# STM32.net
KiCad netlist of a schematic drawn in Altium Designer
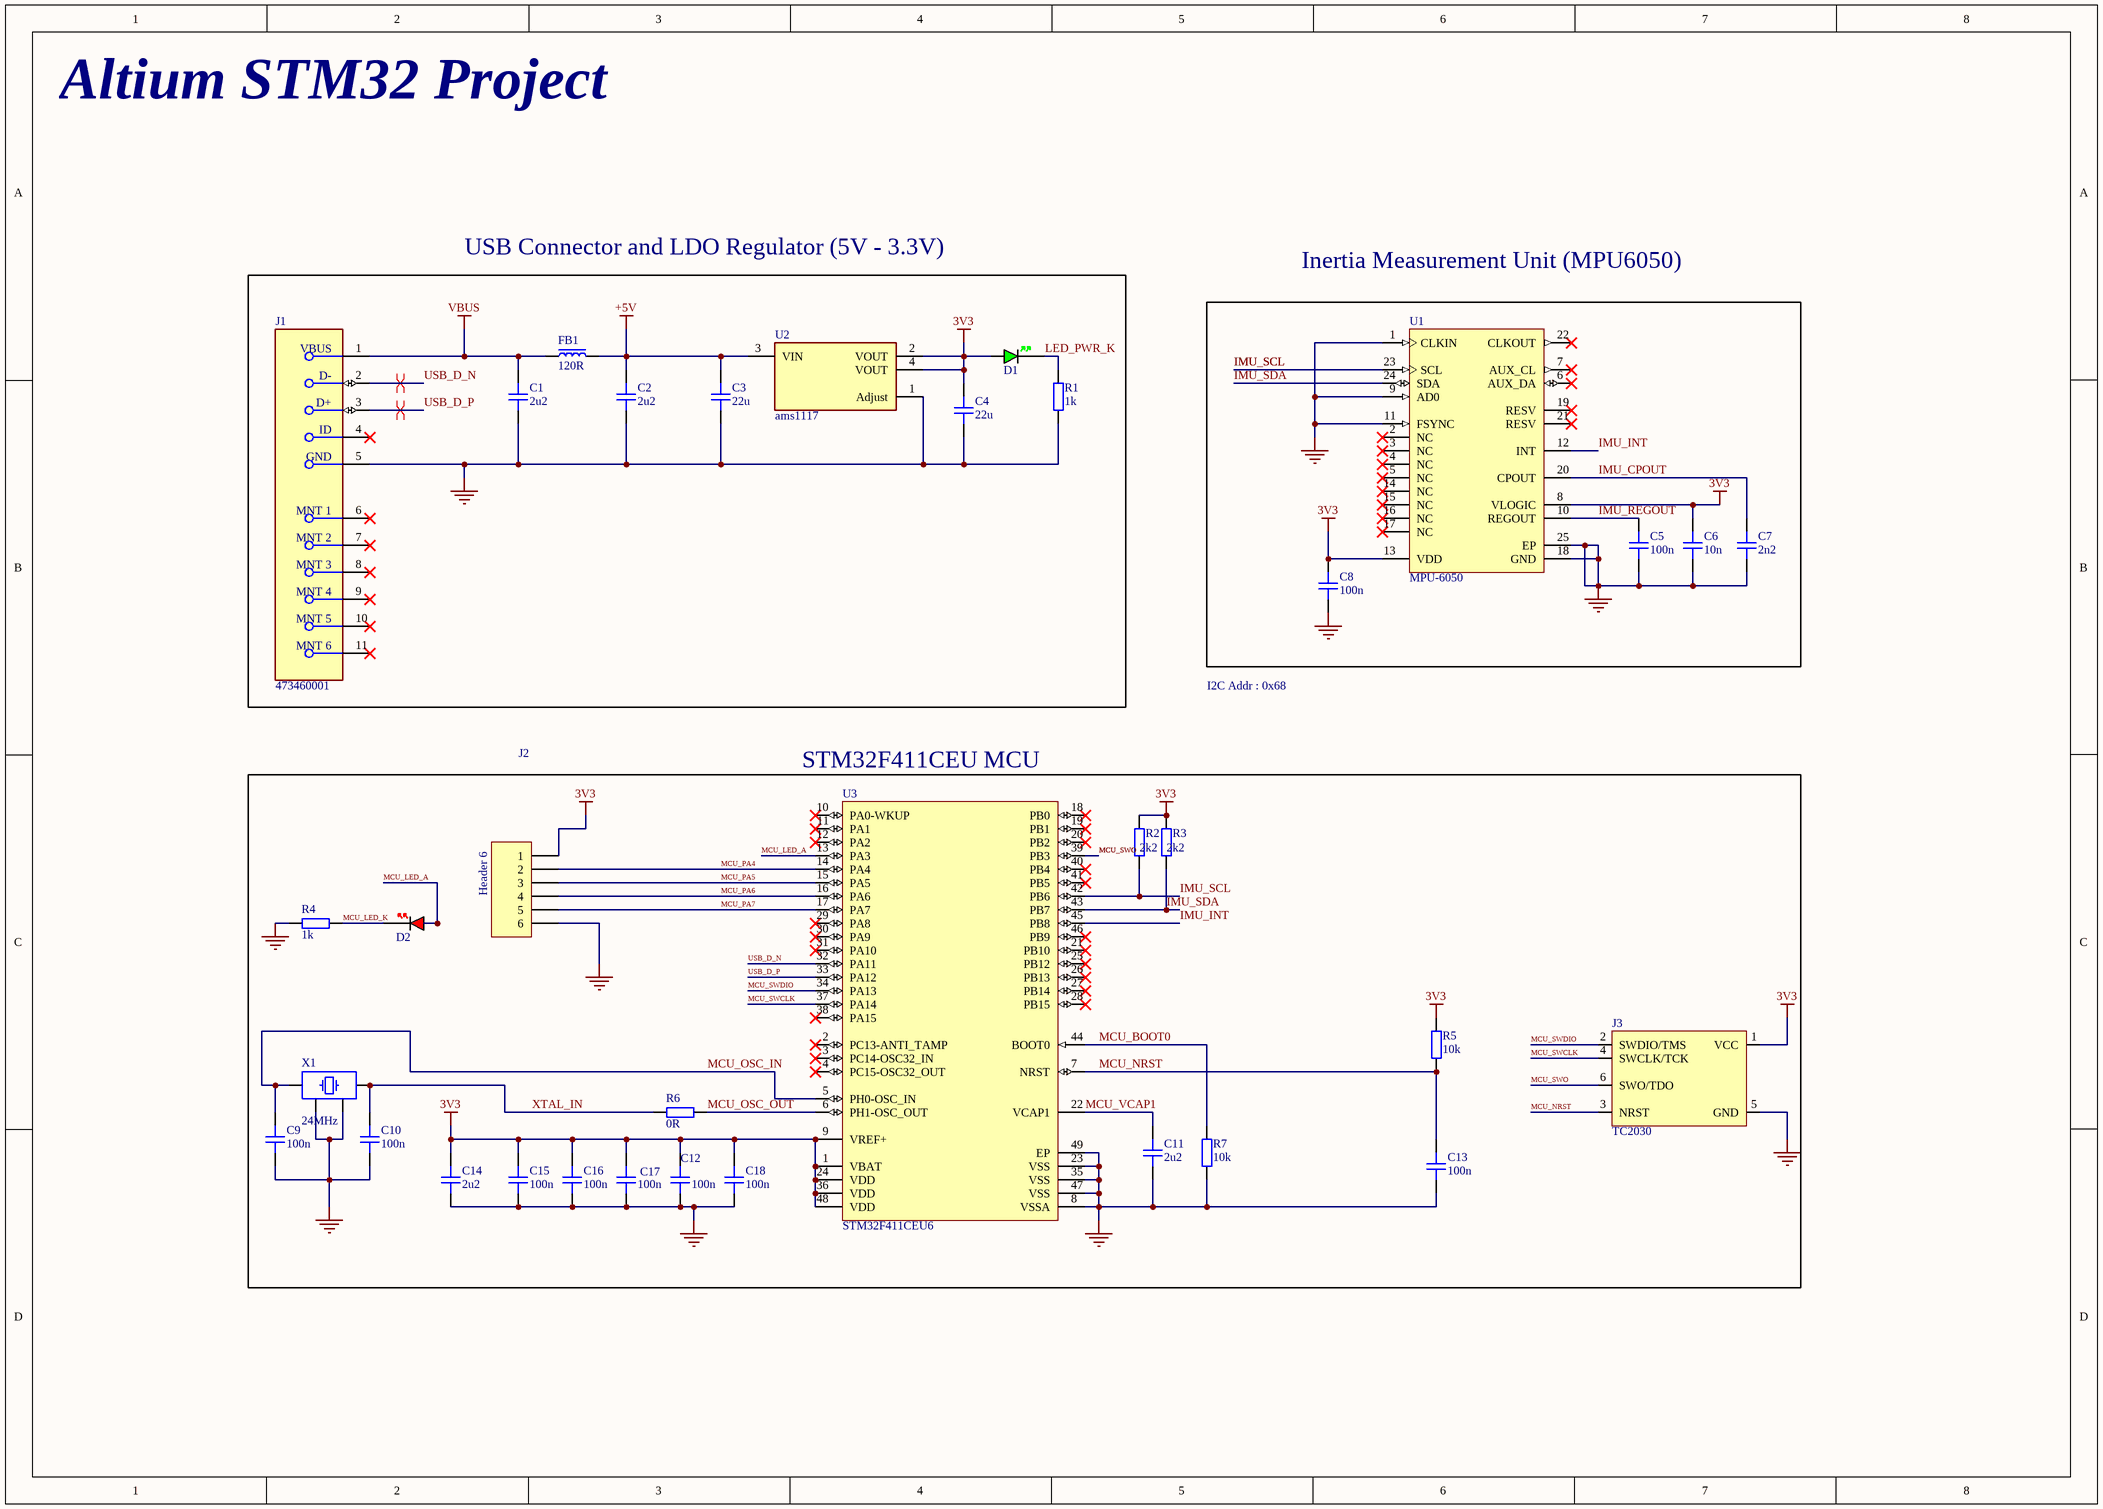
[diagram p0: STM32.SchDoc]

(export (version "E")
  (design (tool "Eeschema 10.0.6"))
  (components
    (comp (ref "C1")
      (value "2u2")
      (footprint "CAP_0603")
      (description "Capacitor SMD 0603")
      (libsource (lib "Schematic-Lib-PhilsLab") (part "CAP_0603"))
    )
    (comp (ref "C2")
      (value "2u2")
      (footprint "CAP_0603")
      (description "Capacitor SMD 0603")
      (libsource (lib "Schematic-Lib-PhilsLab") (part "CAP_0603"))
    )
    (comp (ref "C3")
      (value "22u")
      (footprint "CAP_0805")
      (description "Capacitor SMD 0805")
      (libsource (lib "Schematic-Lib-PhilsLab") (part "CAP_0805"))
    )
    (comp (ref "C4")
      (value "22u")
      (footprint "CAP_0805")
      (description "Capacitor SMD 0805")
      (libsource (lib "Schematic-Lib-PhilsLab") (part "CAP_0805"))
    )
    (comp (ref "C5")
      (value "100n")
      (footprint "CAP_0402")
      (description "Capacitor SMD 0402")
      (libsource (lib "Schematic-Lib-PhilsLab") (part "CAP_0402"))
    )
    (comp (ref "C6")
      (value "10n")
      (footprint "CAP_0402")
      (description "Capacitor SMD 0402")
      (libsource (lib "Schematic-Lib-PhilsLab") (part "CAP_0402"))
    )
    (comp (ref "C7")
      (value "2n2")
      (footprint "CAP_0402")
      (description "Capacitor SMD 0402")
      (libsource (lib "Schematic-Lib-PhilsLab") (part "CAP_0402"))
    )
    (comp (ref "C8")
      (value "100n")
      (footprint "CAP_0402")
      (description "Capacitor SMD 0402")
      (libsource (lib "Schematic-Lib-PhilsLab") (part "CAP_0402"))
    )
    (comp (ref "C9")
      (value "100n")
      (footprint "CAP_0402")
      (description "Capacitor SMD 0402")
      (libsource (lib "Schematic-Lib-PhilsLab") (part "CAP_0402"))
    )
    (comp (ref "C10")
      (value "100n")
      (footprint "CAP_0402")
      (description "Capacitor SMD 0402")
      (libsource (lib "Schematic-Lib-PhilsLab") (part "CAP_0402"))
    )
    (comp (ref "C11")
      (value "2u2")
      (footprint "CAP_0603")
      (description "Capacitor SMD 0603")
      (libsource (lib "Schematic-Lib-PhilsLab") (part "CAP_0603"))
    )
    (comp (ref "C12")
      (value "100n")
      (footprint "CAP_0402")
      (description "Capacitor SMD 0402")
      (libsource (lib "Schematic-Lib-PhilsLab") (part "CAP_0402"))
    )
    (comp (ref "C13")
      (value "100n")
      (footprint "CAP_0402")
      (description "Capacitor SMD 0402")
      (libsource (lib "Schematic-Lib-PhilsLab") (part "CAP_0402"))
    )
    (comp (ref "C14")
      (value "2u2")
      (footprint "CAP_0603")
      (description "Capacitor SMD 0603")
      (libsource (lib "Schematic-Lib-PhilsLab") (part "CAP_0603"))
    )
    (comp (ref "C15")
      (value "100n")
      (footprint "CAP_0402")
      (description "Capacitor SMD 0402")
      (libsource (lib "Schematic-Lib-PhilsLab") (part "CAP_0402"))
    )
    (comp (ref "C16")
      (value "100n")
      (footprint "CAP_0402")
      (description "Capacitor SMD 0402")
      (libsource (lib "Schematic-Lib-PhilsLab") (part "CAP_0402"))
    )
    (comp (ref "C17")
      (value "100n")
      (footprint "CAP_0402")
      (description "Capacitor SMD 0402")
      (libsource (lib "Schematic-Lib-PhilsLab") (part "CAP_0402"))
    )
    (comp (ref "C18")
      (value "100n")
      (footprint "CAP_0402")
      (description "Capacitor SMD 0402")
      (libsource (lib "Schematic-Lib-PhilsLab") (part "CAP_0402"))
    )
    (comp (ref "D1")
      (value "GREEN")
      (footprint "LED_0402_GREEN")
      (description "LED 0402 GREEN SMD")
      (libsource (lib "Schematic-Lib-PhilsLab") (part "LED_0402_GREEN"))
    )
    (comp (ref "D2")
      (value "RED")
      (footprint "LED_0402_RED")
      (description "LED 0402 RED SMD")
      (libsource (lib "Schematic-Lib-PhilsLab") (part "LED_0402_RED"))
    )
    (comp (ref "FB1")
      (value "120R")
      (footprint "FB_0603")
      (description "Ferrite Bead SMD 0603")
      (libsource (lib "Schematic-Lib-PhilsLab") (part "FB_0603"))
    )
    (comp (ref "J1")
      (value "473460001")
      (footprint "FP-473460001-MFG")
      (description "CONN RCPT USB2.0 MICRO B SMD R/A")
      (fields
        (field (name "OCTOPART") "https://octopart.com/47346-0001-molex-7164928")
        (field (name "MANUFACTURER") "Molex")
      )
      (libsource (lib "Altium Content Vault") (part "53ae1f1d9b557310b43ca686e5bb76a"))
    )
    (comp (ref "J2")
      (value "Header 6")
      (footprint "HDR1X6")
      (description "Header, 6-Pin")
      (fields (field (name "PUBLISHER") "Altium Limited"))
      (libsource (lib "Miscellaneous Connectors") (part "Header 6"))
    )
    (comp (ref "J3")
      (value "TC2030")
      (footprint "TC2030-FP")
      (description "Tag-Connect No-Solder SWD Debug Connector DO NOT PLACE")
      (fields (field (name "MANUFACTURER") "Tag-Connect"))
      (libsource (lib "Schematic-Lib-PhilsLab") (part "TC2030"))
    )
    (comp (ref "R1")
      (value "1k")
      (footprint "RES_0402")
      (description "Resistor SMD 0402")
      (libsource (lib "Schematic-Lib-PhilsLab") (part "RES_0402"))
    )
    (comp (ref "R2")
      (value "2k2")
      (footprint "RES_0402")
      (description "Resistor SMD 0402")
      (libsource (lib "Schematic-Lib-PhilsLab") (part "RES_0402"))
    )
    (comp (ref "R3")
      (value "2k2")
      (footprint "RES_0402")
      (description "Resistor SMD 0402")
      (libsource (lib "Schematic-Lib-PhilsLab") (part "RES_0402"))
    )
    (comp (ref "R4")
      (value "1k")
      (footprint "RES_0402")
      (description "Resistor SMD 0402")
      (libsource (lib "Schematic-Lib-PhilsLab") (part "RES_0402"))
    )
    (comp (ref "R5")
      (value "10k")
      (footprint "RES_0402")
      (description "Resistor SMD 0402")
      (libsource (lib "Schematic-Lib-PhilsLab") (part "RES_0402"))
    )
    (comp (ref "R6")
      (value "0R")
      (footprint "RES_0402")
      (description "Resistor SMD 0402")
      (libsource (lib "Schematic-Lib-PhilsLab") (part "RES_0402"))
    )
    (comp (ref "R7")
      (value "10k")
      (footprint "RES_0402")
      (description "Resistor SMD 0402")
      (libsource (lib "Schematic-Lib-PhilsLab") (part "RES_0402"))
    )
    (comp (ref "U1")
      (value "MPU-6050")
      (footprint "IS-QFN-24_V")
      (fields (field (name "MANUFACTURER") "InvenSense"))
      (libsource (lib "Altium Content Vault") (part "IS-MPU-6050-QFN-24"))
    )
    (comp (ref "U2")
      (value "ams1117")
      (footprint "FP-ams1117-IPC_C")
      (description "1A LOW DROPOUT VOLTAGE REGULATOR")
      (libsource (lib "Altium Content Vault") (part "59ad430b93a2c51b3e6ee7c3b069677"))
    )
    (comp (ref "U3")
      (value "STM32F411CEU6")
      (footprint "STM-UFQFPN48_L")
      (libsource (lib "Altium Content Vault") (part "MC-ARM-STM32F411-UFQFPN48"))
    )
    (comp (ref "X1")
      (value "24MHz")
      (footprint "XTAL_3225")
      (description "Crystal SMD 24MHz 10PPM 7pF 3225")
      (fields
        (field (name "MANUFACTURER") "Epson")
        (field (name "MANUFACTURER PART NUMBER") "TSX-3225 24.0000MF15X-AC")
      )
      (libsource (lib "Schematic-Lib-PhilsLab") (part "TSX-3225_24.0000MF15X-AC"))
    )
  )
  (nets
    (net (code "1") (name "+5V") (class "Default")
      (node (ref "C2") (pin "1") (pinfunction "1_1") (pintype "passive"))
      (node (ref "C3") (pin "1") (pinfunction "1_1") (pintype "passive"))
      (node (ref "FB1") (pin "2") (pinfunction "2_2") (pintype "passive"))
      (node (ref "U2") (pin "3") (pinfunction "VIN_3") (pintype "power_in"))
    )
    (net (code "2") (name "/IMU_CPOUT") (class "Default")
      (node (ref "C7") (pin "2") (pinfunction "2_2") (pintype "passive"))
      (node (ref "U1") (pin "20") (pinfunction "CPOUT_20") (pintype "passive"))
    )
    (net (code "3") (name "/IMU_INT") (class "Default")
      (node (ref "U1") (pin "12") (pinfunction "INT_12") (pintype "open_collector"))
      (node (ref "U3") (pin "45") (pinfunction "PB8_45") (pintype "bidirectional"))
    )
    (net (code "4") (name "/IMU_REGOUT") (class "Default")
      (node (ref "C5") (pin "2") (pinfunction "2_2") (pintype "passive"))
      (node (ref "U1") (pin "10") (pinfunction "REGOUT_10") (pintype "passive"))
    )
    (net (code "5") (name "/IMU_SCL") (class "Default")
      (node (ref "R2") (pin "1") (pinfunction "1_1") (pintype "passive"))
      (node (ref "U1") (pin "23") (pinfunction "SCL_23") (pintype "input"))
      (node (ref "U3") (pin "42") (pinfunction "PB6_42") (pintype "bidirectional"))
    )
    (net (code "6") (name "/IMU_SDA") (class "Default")
      (node (ref "R3") (pin "1") (pinfunction "1_1") (pintype "passive"))
      (node (ref "U1") (pin "24") (pinfunction "SDA_24") (pintype "bidirectional"))
      (node (ref "U3") (pin "43") (pinfunction "PB7_43") (pintype "bidirectional"))
    )
    (net (code "7") (name "/LED_PWR_K") (class "Default")
      (node (ref "D1") (pin "K") (pinfunction "K_K") (pintype "passive"))
      (node (ref "R1") (pin "2") (pinfunction "2_2") (pintype "passive"))
    )
    (net (code "8") (name "/MCU_BOOT0") (class "Default")
      (node (ref "R7") (pin "2") (pinfunction "2_2") (pintype "passive"))
      (node (ref "U3") (pin "44") (pinfunction "BOOT0_44") (pintype "input"))
    )
    (net (code "9") (name "/MCU_LED_A") (class "Default")
      (node (ref "D2") (pin "A") (pinfunction "A_A") (pintype "passive"))
      (node (ref "U3") (pin "13") (pinfunction "PA3_13") (pintype "bidirectional"))
    )
    (net (code "10") (name "/MCU_LED_K") (class "Default")
      (node (ref "D2") (pin "K") (pinfunction "K_K") (pintype "passive"))
      (node (ref "R4") (pin "2") (pinfunction "2_2") (pintype "passive"))
    )
    (net (code "11") (name "/MCU_NRST") (class "Default")
      (node (ref "C13") (pin "2") (pinfunction "2_2") (pintype "passive"))
      (node (ref "J3") (pin "3") (pinfunction "NRST_3") (pintype "passive"))
      (node (ref "R5") (pin "1") (pinfunction "1_1") (pintype "passive"))
      (node (ref "U3") (pin "7") (pinfunction "NRST_7") (pintype "bidirectional"))
    )
    (net (code "12") (name "/MCU_OSC_IN") (class "Default")
      (node (ref "C9") (pin "2") (pinfunction "2_2") (pintype "passive"))
      (node (ref "U3") (pin "5") (pinfunction "PH0-OSC_IN_5") (pintype "bidirectional"))
      (node (ref "X1") (pin "1") (pinfunction "1_1") (pintype "passive"))
    )
    (net (code "13") (name "/MCU_OSC_OUT") (class "Default")
      (node (ref "R6") (pin "1") (pinfunction "1_1") (pintype "passive"))
      (node (ref "U3") (pin "6") (pinfunction "PH1-OSC_OUT_6") (pintype "bidirectional"))
    )
    (net (code "14") (name "/MCU_PA4") (class "Default")
      (node (ref "J2") (pin "2") (pinfunction "2_2") (pintype "passive"))
      (node (ref "U3") (pin "14") (pinfunction "PA4_14") (pintype "bidirectional"))
    )
    (net (code "15") (name "/MCU_PA5") (class "Default")
      (node (ref "J2") (pin "3") (pinfunction "3_3") (pintype "passive"))
      (node (ref "U3") (pin "15") (pinfunction "PA5_15") (pintype "bidirectional"))
    )
    (net (code "16") (name "/MCU_PA6") (class "Default")
      (node (ref "J2") (pin "4") (pinfunction "4_4") (pintype "passive"))
      (node (ref "U3") (pin "16") (pinfunction "PA6_16") (pintype "bidirectional"))
    )
    (net (code "17") (name "/MCU_PA7") (class "Default")
      (node (ref "J2") (pin "5") (pinfunction "5_5") (pintype "passive"))
      (node (ref "U3") (pin "17") (pinfunction "PA7_17") (pintype "bidirectional"))
    )
    (net (code "18") (name "/MCU_SWCLK") (class "Default")
      (node (ref "J3") (pin "4") (pinfunction "SWCLK/TCK_4") (pintype "passive"))
      (node (ref "U3") (pin "37") (pinfunction "PA14_37") (pintype "bidirectional"))
    )
    (net (code "19") (name "/MCU_SWDIO") (class "Default")
      (node (ref "J3") (pin "2") (pinfunction "SWDIO/TMS_2") (pintype "passive"))
      (node (ref "U3") (pin "34") (pinfunction "PA13_34") (pintype "bidirectional"))
    )
    (net (code "20") (name "/MCU_SWO") (class "Default")
      (node (ref "J3") (pin "6") (pinfunction "SWO/TDO_6") (pintype "passive"))
      (node (ref "U3") (pin "39") (pinfunction "PB3_39") (pintype "bidirectional"))
    )
    (net (code "21") (name "/MCU_VCAP1") (class "Default")
      (node (ref "C11") (pin "1") (pinfunction "1_1") (pintype "passive"))
      (node (ref "U3") (pin "22") (pinfunction "VCAP1_22") (pintype "passive"))
    )
    (net (code "22") (name "/USB_D_N") (class "Default")
      (node (ref "J1") (pin "2") (pinfunction "D-_2") (pintype "bidirectional"))
      (node (ref "U3") (pin "32") (pinfunction "PA11_32") (pintype "bidirectional"))
    )
    (net (code "23") (name "/USB_D_P") (class "Default")
      (node (ref "J1") (pin "3") (pinfunction "D+_3") (pintype "bidirectional"))
      (node (ref "U3") (pin "33") (pinfunction "PA12_33") (pintype "bidirectional"))
    )
    (net (code "24") (name "/XTAL_IN") (class "Default")
      (node (ref "C10") (pin "2") (pinfunction "2_2") (pintype "passive"))
      (node (ref "R6") (pin "2") (pinfunction "2_2") (pintype "passive"))
      (node (ref "X1") (pin "3") (pinfunction "3_3") (pintype "passive"))
    )
    (net (code "25") (name "3V3") (class "Default")
      (node (ref "C12") (pin "2") (pinfunction "2_2") (pintype "passive"))
      (node (ref "C14") (pin "1") (pinfunction "1_1") (pintype "passive"))
      (node (ref "C15") (pin "2") (pinfunction "2_2") (pintype "passive"))
      (node (ref "C16") (pin "2") (pinfunction "2_2") (pintype "passive"))
      (node (ref "C17") (pin "2") (pinfunction "2_2") (pintype "passive"))
      (node (ref "C18") (pin "2") (pinfunction "2_2") (pintype "passive"))
      (node (ref "C4") (pin "1") (pinfunction "1_1") (pintype "passive"))
      (node (ref "C6") (pin "2") (pinfunction "2_2") (pintype "passive"))
      (node (ref "C8") (pin "2") (pinfunction "2_2") (pintype "passive"))
      (node (ref "D1") (pin "A") (pinfunction "A_A") (pintype "passive"))
      (node (ref "J2") (pin "1") (pinfunction "1_1") (pintype "passive"))
      (node (ref "J3") (pin "1") (pinfunction "VCC_1") (pintype "passive"))
      (node (ref "R2") (pin "2") (pinfunction "2_2") (pintype "passive"))
      (node (ref "R3") (pin "2") (pinfunction "2_2") (pintype "passive"))
      (node (ref "R5") (pin "2") (pinfunction "2_2") (pintype "passive"))
      (node (ref "U1") (pin "13") (pinfunction "VDD_13") (pintype "power_in"))
      (node (ref "U1") (pin "8") (pinfunction "VLOGIC_8") (pintype "power_in"))
      (node (ref "U2") (pin "2") (pinfunction "VOUT_2") (pintype "passive"))
      (node (ref "U2") (pin "4") (pinfunction "VOUT_4") (pintype "passive"))
      (node (ref "U3") (pin "1") (pinfunction "VBAT_1") (pintype "power_in"))
      (node (ref "U3") (pin "24") (pinfunction "VDD_24") (pintype "power_in"))
      (node (ref "U3") (pin "36") (pinfunction "VDD_36") (pintype "power_in"))
      (node (ref "U3") (pin "48") (pinfunction "VDD_48") (pintype "power_in"))
      (node (ref "U3") (pin "9") (pinfunction "VREF+_9") (pintype "power_in"))
    )
    (net (code "26") (name "GND") (class "Default")
      (node (ref "C1") (pin "2") (pinfunction "2_2") (pintype "passive"))
      (node (ref "C10") (pin "1") (pinfunction "1_1") (pintype "passive"))
      (node (ref "C11") (pin "2") (pinfunction "2_2") (pintype "passive"))
      (node (ref "C12") (pin "1") (pinfunction "1_1") (pintype "passive"))
      (node (ref "C13") (pin "1") (pinfunction "1_1") (pintype "passive"))
      (node (ref "C14") (pin "2") (pinfunction "2_2") (pintype "passive"))
      (node (ref "C15") (pin "1") (pinfunction "1_1") (pintype "passive"))
      (node (ref "C16") (pin "1") (pinfunction "1_1") (pintype "passive"))
      (node (ref "C17") (pin "1") (pinfunction "1_1") (pintype "passive"))
      (node (ref "C18") (pin "1") (pinfunction "1_1") (pintype "passive"))
      (node (ref "C2") (pin "2") (pinfunction "2_2") (pintype "passive"))
      (node (ref "C3") (pin "2") (pinfunction "2_2") (pintype "passive"))
      (node (ref "C4") (pin "2") (pinfunction "2_2") (pintype "passive"))
      (node (ref "C5") (pin "1") (pinfunction "1_1") (pintype "passive"))
      (node (ref "C6") (pin "1") (pinfunction "1_1") (pintype "passive"))
      (node (ref "C7") (pin "1") (pinfunction "1_1") (pintype "passive"))
      (node (ref "C8") (pin "1") (pinfunction "1_1") (pintype "passive"))
      (node (ref "C9") (pin "1") (pinfunction "1_1") (pintype "passive"))
      (node (ref "J1") (pin "5") (pinfunction "GND_5") (pintype "power_in"))
      (node (ref "J2") (pin "6") (pinfunction "6_6") (pintype "passive"))
      (node (ref "J3") (pin "5") (pinfunction "GND_5") (pintype "passive"))
      (node (ref "R1") (pin "1") (pinfunction "1_1") (pintype "passive"))
      (node (ref "R4") (pin "1") (pinfunction "1_1") (pintype "passive"))
      (node (ref "R7") (pin "1") (pinfunction "1_1") (pintype "passive"))
      (node (ref "U1") (pin "1") (pinfunction "CLKIN_1") (pintype "input"))
      (node (ref "U1") (pin "11") (pinfunction "FSYNC_11") (pintype "input"))
      (node (ref "U1") (pin "18") (pinfunction "GND_18") (pintype "power_in"))
      (node (ref "U1") (pin "25") (pinfunction "EP_25") (pintype "power_in"))
      (node (ref "U1") (pin "9") (pinfunction "AD0_9") (pintype "input"))
      (node (ref "U2") (pin "1") (pinfunction "Adjust_1") (pintype "passive"))
      (node (ref "U3") (pin "23") (pinfunction "VSS_23") (pintype "power_in"))
      (node (ref "U3") (pin "35") (pinfunction "VSS_35") (pintype "power_in"))
      (node (ref "U3") (pin "47") (pinfunction "VSS_47") (pintype "power_in"))
      (node (ref "U3") (pin "49") (pinfunction "EP_49") (pintype "power_in"))
      (node (ref "U3") (pin "8") (pinfunction "VSSA_8") (pintype "power_in"))
      (node (ref "X1") (pin "2") (pinfunction "2_2") (pintype "passive"))
      (node (ref "X1") (pin "4") (pinfunction "4_4") (pintype "passive"))
    )
    (net (code "27") (name "VBUS") (class "Default")
      (node (ref "C1") (pin "1") (pinfunction "1_1") (pintype "passive"))
      (node (ref "FB1") (pin "1") (pinfunction "1_1") (pintype "passive"))
      (node (ref "J1") (pin "1") (pinfunction "VBUS_1") (pintype "power_in"))
    )
    (net (code "28") (name "unconnected-(J1-ID-Pad4)") (class "Default")
      (node (ref "J1") (pin "4") (pinfunction "ID_4") (pintype "passive+no_connect"))
    )
    (net (code "29") (name "unconnected-(J1-MNT_1-Pad6)") (class "Default")
      (node (ref "J1") (pin "6") (pinfunction "MNT_1_6") (pintype "passive+no_connect"))
    )
    (net (code "30") (name "unconnected-(J1-MNT_2-Pad7)") (class "Default")
      (node (ref "J1") (pin "7") (pinfunction "MNT_2_7") (pintype "passive+no_connect"))
    )
    (net (code "31") (name "unconnected-(J1-MNT_3-Pad8)") (class "Default")
      (node (ref "J1") (pin "8") (pinfunction "MNT_3_8") (pintype "passive+no_connect"))
    )
    (net (code "32") (name "unconnected-(J1-MNT_4-Pad9)") (class "Default")
      (node (ref "J1") (pin "9") (pinfunction "MNT_4_9") (pintype "passive+no_connect"))
    )
    (net (code "33") (name "unconnected-(J1-MNT_5-Pad10)") (class "Default")
      (node (ref "J1") (pin "10") (pinfunction "MNT_5_10") (pintype "passive+no_connect"))
    )
    (net (code "34") (name "unconnected-(J1-MNT_6-Pad11)") (class "Default")
      (node (ref "J1") (pin "11") (pinfunction "MNT_6_11") (pintype "passive+no_connect"))
    )
    (net (code "35") (name "unconnected-(U1-AUX_CL-Pad7)") (class "Default")
      (node (ref "U1") (pin "7") (pinfunction "AUX_CL_7") (pintype "output+no_connect"))
    )
    (net (code "36") (name "unconnected-(U1-AUX_DA-Pad6)") (class "Default")
      (node (ref "U1") (pin "6") (pinfunction "AUX_DA_6") (pintype "bidirectional+no_connect"))
    )
    (net (code "37") (name "unconnected-(U1-CLKOUT-Pad22)") (class "Default")
      (node (ref "U1") (pin "22") (pinfunction "CLKOUT_22") (pintype "output+no_connect"))
    )
    (net (code "38") (name "unconnected-(U1-NC-Pad2)") (class "Default")
      (node (ref "U1") (pin "2") (pinfunction "NC_2") (pintype "passive+no_connect"))
    )
    (net (code "39") (name "unconnected-(U1-NC-Pad3)") (class "Default")
      (node (ref "U1") (pin "3") (pinfunction "NC_3") (pintype "passive+no_connect"))
    )
    (net (code "40") (name "unconnected-(U1-NC-Pad4)") (class "Default")
      (node (ref "U1") (pin "4") (pinfunction "NC_4") (pintype "passive+no_connect"))
    )
    (net (code "41") (name "unconnected-(U1-NC-Pad5)") (class "Default")
      (node (ref "U1") (pin "5") (pinfunction "NC_5") (pintype "passive+no_connect"))
    )
    (net (code "42") (name "unconnected-(U1-NC-Pad14)") (class "Default")
      (node (ref "U1") (pin "14") (pinfunction "NC_14") (pintype "passive+no_connect"))
    )
    (net (code "43") (name "unconnected-(U1-NC-Pad15)") (class "Default")
      (node (ref "U1") (pin "15") (pinfunction "NC_15") (pintype "passive+no_connect"))
    )
    (net (code "44") (name "unconnected-(U1-NC-Pad16)") (class "Default")
      (node (ref "U1") (pin "16") (pinfunction "NC_16") (pintype "passive+no_connect"))
    )
    (net (code "45") (name "unconnected-(U1-NC-Pad17)") (class "Default")
      (node (ref "U1") (pin "17") (pinfunction "NC_17") (pintype "passive+no_connect"))
    )
    (net (code "46") (name "unconnected-(U1-RESV-Pad19)") (class "Default")
      (node (ref "U1") (pin "19") (pinfunction "RESV_19") (pintype "passive+no_connect"))
    )
    (net (code "47") (name "unconnected-(U1-RESV-Pad21)") (class "Default")
      (node (ref "U1") (pin "21") (pinfunction "RESV_21") (pintype "passive+no_connect"))
    )
    (net (code "48") (name "unconnected-(U3-PA0-WKUP-Pad10)") (class "Default")
      (node (ref "U3") (pin "10") (pinfunction "PA0-WKUP_10") (pintype "bidirectional+no_connect"))
    )
    (net (code "49") (name "unconnected-(U3-PA1-Pad11)") (class "Default")
      (node (ref "U3") (pin "11") (pinfunction "PA1_11") (pintype "bidirectional+no_connect"))
    )
    (net (code "50") (name "unconnected-(U3-PA2-Pad12)") (class "Default")
      (node (ref "U3") (pin "12") (pinfunction "PA2_12") (pintype "bidirectional+no_connect"))
    )
    (net (code "51") (name "unconnected-(U3-PA8-Pad29)") (class "Default")
      (node (ref "U3") (pin "29") (pinfunction "PA8_29") (pintype "bidirectional+no_connect"))
    )
    (net (code "52") (name "unconnected-(U3-PA9-Pad30)") (class "Default")
      (node (ref "U3") (pin "30") (pinfunction "PA9_30") (pintype "bidirectional+no_connect"))
    )
    (net (code "53") (name "unconnected-(U3-PA10-Pad31)") (class "Default")
      (node (ref "U3") (pin "31") (pinfunction "PA10_31") (pintype "bidirectional+no_connect"))
    )
    (net (code "54") (name "unconnected-(U3-PA15-Pad38)") (class "Default")
      (node (ref "U3") (pin "38") (pinfunction "PA15_38") (pintype "bidirectional+no_connect"))
    )
    (net (code "55") (name "unconnected-(U3-PB0-Pad18)") (class "Default")
      (node (ref "U3") (pin "18") (pinfunction "PB0_18") (pintype "bidirectional+no_connect"))
    )
    (net (code "56") (name "unconnected-(U3-PB1-Pad19)") (class "Default")
      (node (ref "U3") (pin "19") (pinfunction "PB1_19") (pintype "bidirectional+no_connect"))
    )
    (net (code "57") (name "unconnected-(U3-PB2-Pad20)") (class "Default")
      (node (ref "U3") (pin "20") (pinfunction "PB2_20") (pintype "bidirectional+no_connect"))
    )
    (net (code "58") (name "unconnected-(U3-PB4-Pad40)") (class "Default")
      (node (ref "U3") (pin "40") (pinfunction "PB4_40") (pintype "bidirectional+no_connect"))
    )
    (net (code "59") (name "unconnected-(U3-PB5-Pad41)") (class "Default")
      (node (ref "U3") (pin "41") (pinfunction "PB5_41") (pintype "bidirectional+no_connect"))
    )
    (net (code "60") (name "unconnected-(U3-PB9-Pad46)") (class "Default")
      (node (ref "U3") (pin "46") (pinfunction "PB9_46") (pintype "bidirectional+no_connect"))
    )
    (net (code "61") (name "unconnected-(U3-PB10-Pad21)") (class "Default")
      (node (ref "U3") (pin "21") (pinfunction "PB10_21") (pintype "bidirectional+no_connect"))
    )
    (net (code "62") (name "unconnected-(U3-PB12-Pad25)") (class "Default")
      (node (ref "U3") (pin "25") (pinfunction "PB12_25") (pintype "bidirectional+no_connect"))
    )
    (net (code "63") (name "unconnected-(U3-PB13-Pad26)") (class "Default")
      (node (ref "U3") (pin "26") (pinfunction "PB13_26") (pintype "bidirectional+no_connect"))
    )
    (net (code "64") (name "unconnected-(U3-PB14-Pad27)") (class "Default")
      (node (ref "U3") (pin "27") (pinfunction "PB14_27") (pintype "bidirectional+no_connect"))
    )
    (net (code "65") (name "unconnected-(U3-PB15-Pad28)") (class "Default")
      (node (ref "U3") (pin "28") (pinfunction "PB15_28") (pintype "bidirectional+no_connect"))
    )
    (net (code "66") (name "unconnected-(U3-PC13-ANTI_TAMP-Pad2)") (class "Default")
      (node (ref "U3") (pin "2") (pinfunction "PC13-ANTI_TAMP_2") (pintype "bidirectional+no_connect"))
    )
    (net (code "67") (name "unconnected-(U3-PC14-OSC32_IN-Pad3)") (class "Default")
      (node (ref "U3") (pin "3") (pinfunction "PC14-OSC32_IN_3") (pintype "bidirectional+no_connect"))
    )
    (net (code "68") (name "unconnected-(U3-PC15-OSC32_OUT-Pad4)") (class "Default")
      (node (ref "U3") (pin "4") (pinfunction "PC15-OSC32_OUT_4") (pintype "bidirectional+no_connect"))
    )
  )
)
